# working.net
KiCad netlist of a schematic drawn in EAGLE
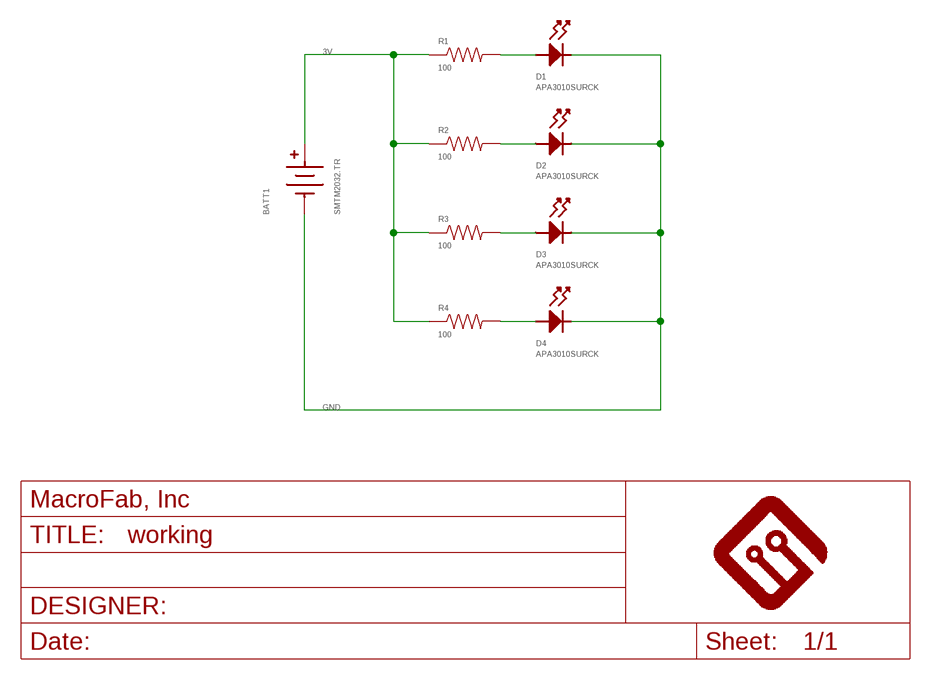
[diagram p0: schematic, sheet 1]

(export (version "E")
  (design (tool "Eeschema 10.0.6"))
  (components
    (comp (ref "BATT1")
      (value "SMTM2032.TR")
      (footprint "eagle-import:SMTM2032")
      (libsource (lib "eagle-import") (part "BATTERYSMTM2032"))
    )
    (comp (ref "D1")
      (value "APA3010SURCK")
      (footprint "eagle-import:APA3010")
      (libsource (lib "eagle-import") (part "LED_SINGLEAPA3010"))
    )
    (comp (ref "D2")
      (value "APA3010SURCK")
      (footprint "eagle-import:APA3010")
      (libsource (lib "eagle-import") (part "LED_SINGLEAPA3010"))
    )
    (comp (ref "D3")
      (value "APA3010SURCK")
      (footprint "eagle-import:APA3010")
      (libsource (lib "eagle-import") (part "LED_SINGLEAPA3010"))
    )
    (comp (ref "D4")
      (value "APA3010SURCK")
      (footprint "eagle-import:APA3010")
      (libsource (lib "eagle-import") (part "LED_SINGLEAPA3010"))
    )
    (comp (ref "R1")
      (value "100")
      (footprint "eagle-import:0805")
      (libsource (lib "eagle-import") (part "RESISTOR0805"))
    )
    (comp (ref "R2")
      (value "100")
      (footprint "eagle-import:0805")
      (libsource (lib "eagle-import") (part "RESISTOR0805"))
    )
    (comp (ref "R3")
      (value "100")
      (footprint "eagle-import:0805")
      (libsource (lib "eagle-import") (part "RESISTOR0805"))
    )
    (comp (ref "R4")
      (value "100")
      (footprint "eagle-import:0805")
      (libsource (lib "eagle-import") (part "RESISTOR0805"))
    )
    (comp (ref "U$1")
      (value "MF_FRAMEMF_FRAME")
      (footprint "eagle-import:MF_FRAME")
      (fields (field (name "DNAME") "Parker Dillmann") (field (name "REVNUM") "REV 0"))
      (libsource (lib "eagle-import") (part "MF_FRAMEMF_FRAME"))
    )
  )
  (nets
    (net (code "1") (name "/3V") (class "Default")
      (node (ref "BATT1") (pin "BATT+_0") (pinfunction "+_BATT+_0") (pintype "bidirectional"))
      (node (ref "BATT1") (pin "BATT+_1") (pinfunction "+_BATT+_1") (pintype "bidirectional"))
      (node (ref "R1") (pin "1") (pinfunction "1_1") (pintype "passive"))
      (node (ref "R2") (pin "1") (pinfunction "1_1") (pintype "passive"))
      (node (ref "R3") (pin "1") (pinfunction "1_1") (pintype "passive"))
      (node (ref "R4") (pin "1") (pinfunction "1_1") (pintype "passive"))
    )
    (net (code "2") (name "/GND") (class "Default")
      (node (ref "BATT1") (pin "BATT-") (pinfunction "-_BATT-") (pintype "bidirectional"))
      (node (ref "D1") (pin "1") (pinfunction "CATHODE_1") (pintype "bidirectional"))
      (node (ref "D2") (pin "1") (pinfunction "CATHODE_1") (pintype "bidirectional"))
      (node (ref "D3") (pin "1") (pinfunction "CATHODE_1") (pintype "bidirectional"))
      (node (ref "D4") (pin "1") (pinfunction "CATHODE_1") (pintype "bidirectional"))
    )
    (net (code "3") (name "Net-(D1-ANODE)") (class "Default")
      (node (ref "D1") (pin "2") (pinfunction "ANODE_2") (pintype "bidirectional"))
      (node (ref "R1") (pin "2") (pinfunction "2_2") (pintype "passive"))
    )
    (net (code "4") (name "Net-(D2-ANODE)") (class "Default")
      (node (ref "D2") (pin "2") (pinfunction "ANODE_2") (pintype "bidirectional"))
      (node (ref "R2") (pin "2") (pinfunction "2_2") (pintype "passive"))
    )
    (net (code "5") (name "Net-(D3-ANODE)") (class "Default")
      (node (ref "D3") (pin "2") (pinfunction "ANODE_2") (pintype "bidirectional"))
      (node (ref "R3") (pin "2") (pinfunction "2_2") (pintype "passive"))
    )
    (net (code "6") (name "Net-(D4-ANODE)") (class "Default")
      (node (ref "D4") (pin "2") (pinfunction "ANODE_2") (pintype "bidirectional"))
      (node (ref "R4") (pin "2") (pinfunction "2_2") (pintype "passive"))
    )
  )
)
